# EasyEDA_Source.net
KiCad netlist of a schematic drawn in EasyEDA
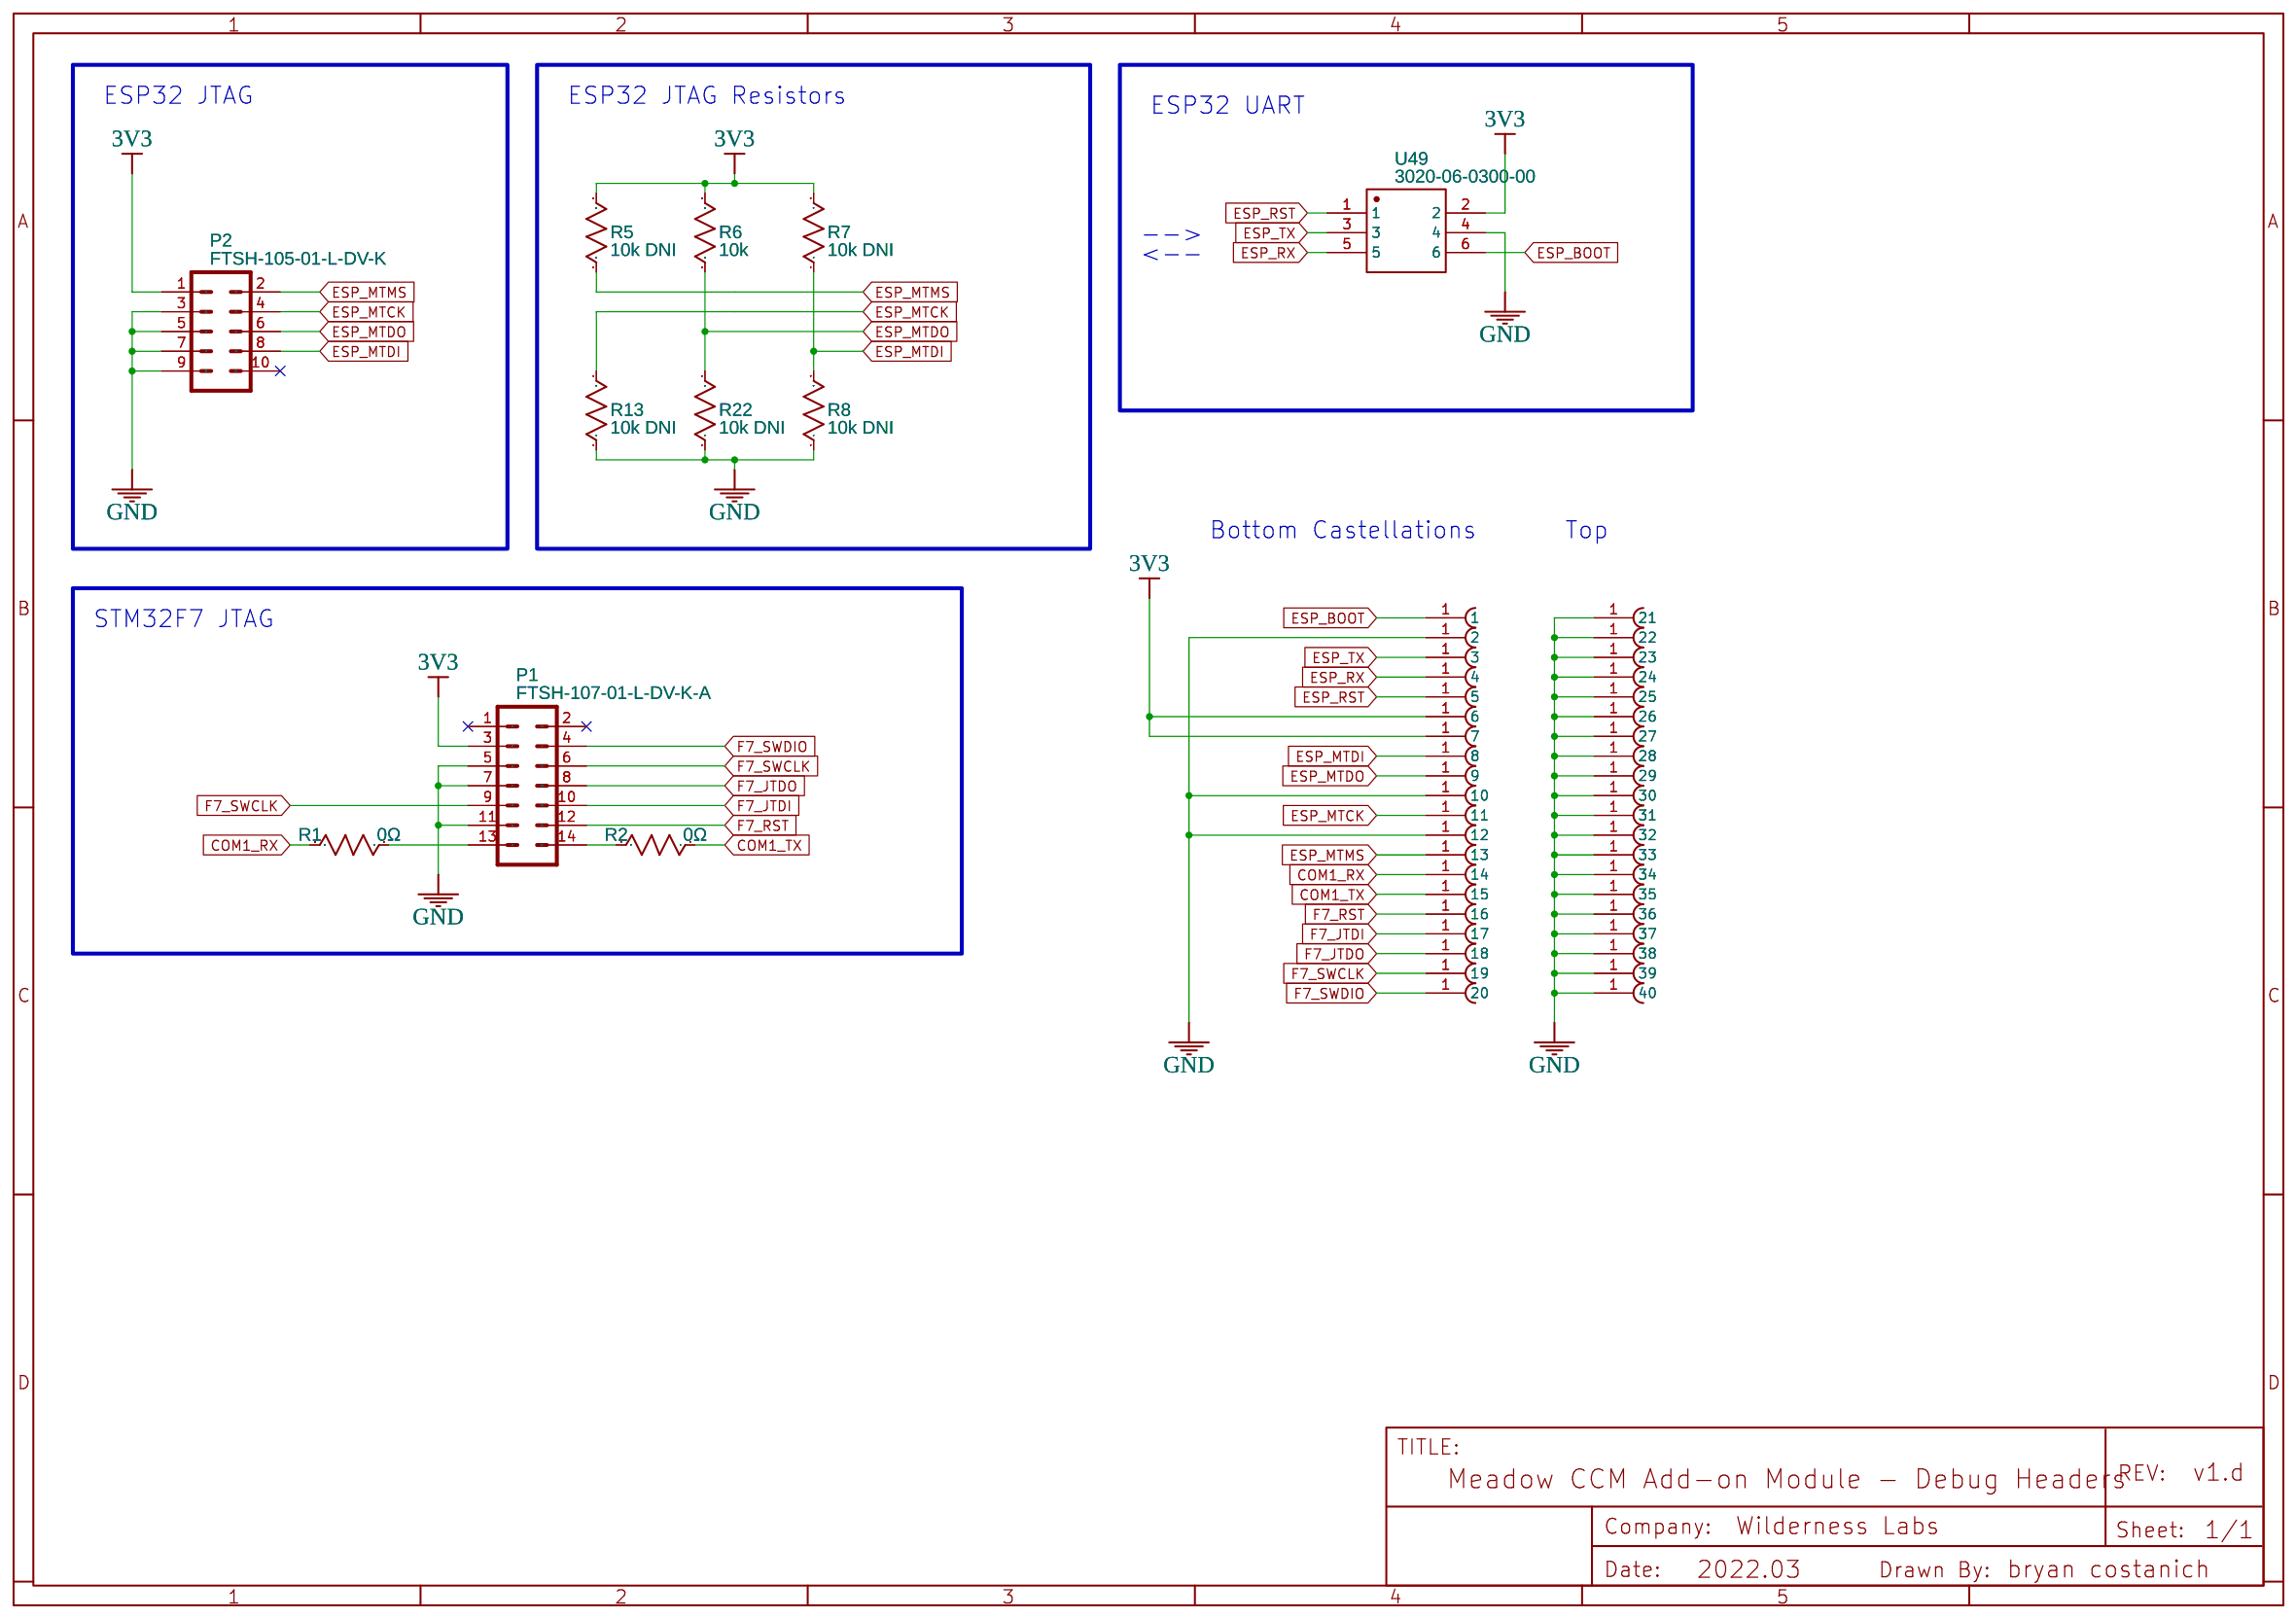
[diagram p0: schematic sheet]

(export (version "E")
  (design (tool "Eeschema 10.0.6"))
  (components
    (comp (ref "P1") (value "FTSH-107-01-L-DV-K-A") (libsource (lib "") (part "FTSH-107-01-L-DV-K-A")))
    (comp (ref "P2") (value "FTSH-105-01-L-DV-K") (libsource (lib "") (part "FTSH-105-01-L-DV-K")))
    (comp (ref "R1")
      (value "0Ω")
      (fields (field (name "BOM_Manufacturer Part") "RC0603JR-070RL"))
      (libsource (lib "") (part "R_0603_US_1"))
    )
    (comp (ref "R2")
      (value "0Ω")
      (fields (field (name "BOM_Manufacturer Part") "RC0603JR-070RL"))
      (libsource (lib "") (part "R_0603_US_1"))
    )
    (comp (ref "R5")
      (value "10k DNI")
      (fields (field (name "BOM_Manufacturer Part") "RC0603FR-0710KL"))
      (libsource (lib "") (part "R_0603_US"))
    )
    (comp (ref "R6")
      (value "10k")
      (fields (field (name "BOM_Manufacturer Part") "RC0603FR-0710KL"))
      (libsource (lib "") (part "R_0603_US"))
    )
    (comp (ref "R7")
      (value "10k DNI")
      (fields (field (name "BOM_Manufacturer Part") "RC0603FR-0710KL"))
      (libsource (lib "") (part "R_0603_US"))
    )
    (comp (ref "R8")
      (value "10k DNI")
      (fields (field (name "BOM_Manufacturer Part") "RC0603FR-0710KL"))
      (libsource (lib "") (part "R_0603_US"))
    )
    (comp (ref "R13")
      (value "10k DNI")
      (fields (field (name "BOM_Manufacturer Part") "RC0603FR-0710KL"))
      (libsource (lib "") (part "R_0603_US"))
    )
    (comp (ref "R22")
      (value "10k DNI")
      (fields (field (name "BOM_Manufacturer Part") "RC0603FR-0710KL"))
      (libsource (lib "") (part "R_0603_US"))
    )
    (comp (ref "U1") (value "1.2MM SMT Castellation") (libsource (lib "") (part "1.2MM SMT Castellation_32")))
    (comp (ref "U2") (value "1.2MM SMT Castellation") (libsource (lib "") (part "1.2MM SMT Castellation_23")))
    (comp (ref "U3") (value "1.2MM SMT Castellation") (libsource (lib "") (part "1.2MM SMT Castellation_8")))
    (comp (ref "U4") (value "1.2MM SMT Castellation") (libsource (lib "") (part "1.2MM SMT Castellation_4")))
    (comp (ref "U5") (value "1.2MM SMT Castellation") (libsource (lib "") (part "1.2MM SMT Castellation_28")))
    (comp (ref "U6") (value "1.2MM SMT Castellation") (libsource (lib "") (part "1.2MM SMT Castellation_26")))
    (comp (ref "U7") (value "1.2MM SMT Castellation") (libsource (lib "") (part "1.2MM SMT Castellation_31")))
    (comp (ref "U8") (value "1.2MM SMT Castellation") (libsource (lib "") (part "1.2MM SMT Castellation_10")))
    (comp (ref "U9") (value "1.2MM SMT Castellation") (libsource (lib "") (part "1.2MM SMT Castellation_35")))
    (comp (ref "U10") (value "1.2MM SMT Castellation") (libsource (lib "") (part "1.2MM SMT Castellation_9")))
    (comp (ref "U11")
      (value "1.2MM SMT Castellation")
      (libsource (lib "") (part "1.2MM SMT Castellation_16"))
    )
    (comp (ref "U12")
      (value "1.2MM SMT Castellation")
      (libsource (lib "") (part "1.2MM SMT Castellation_37"))
    )
    (comp (ref "U13") (value "1.2MM SMT Castellation") (libsource (lib "") (part "1.2MM SMT Castellation_7")))
    (comp (ref "U14")
      (value "1.2MM SMT Castellation")
      (libsource (lib "") (part "1.2MM SMT Castellation_14"))
    )
    (comp (ref "U15") (value "1.2MM SMT Castellation") (libsource (lib "") (part "1.2MM SMT Castellation_3")))
    (comp (ref "U16")
      (value "1.2MM SMT Castellation")
      (libsource (lib "") (part "1.2MM SMT Castellation_22"))
    )
    (comp (ref "U17")
      (value "1.2MM SMT Castellation")
      (libsource (lib "") (part "1.2MM SMT Castellation_18"))
    )
    (comp (ref "U18")
      (value "1.2MM SMT Castellation")
      (libsource (lib "") (part "1.2MM SMT Castellation_13"))
    )
    (comp (ref "U19")
      (value "1.2MM SMT Castellation")
      (libsource (lib "") (part "1.2MM SMT Castellation_34"))
    )
    (comp (ref "U20")
      (value "1.2MM SMT Castellation")
      (libsource (lib "") (part "1.2MM SMT Castellation_11"))
    )
    (comp (ref "U21")
      (value "1.2MM SMT Castellation")
      (libsource (lib "") (part "1.2MM SMT Castellation_39"))
    )
    (comp (ref "U22") (value "1.2MM SMT Castellation") (libsource (lib "") (part "1.2MM SMT Castellation_5")))
    (comp (ref "U23")
      (value "1.2MM SMT Castellation")
      (libsource (lib "") (part "1.2MM SMT Castellation_25"))
    )
    (comp (ref "U24")
      (value "1.2MM SMT Castellation")
      (libsource (lib "") (part "1.2MM SMT Castellation_36"))
    )
    (comp (ref "U25")
      (value "1.2MM SMT Castellation")
      (libsource (lib "") (part "1.2MM SMT Castellation_19"))
    )
    (comp (ref "U26")
      (value "1.2MM SMT Castellation")
      (libsource (lib "") (part "1.2MM SMT Castellation_33"))
    )
    (comp (ref "U27")
      (value "1.2MM SMT Castellation")
      (libsource (lib "") (part "1.2MM SMT Castellation_30"))
    )
    (comp (ref "U28")
      (value "1.2MM SMT Castellation")
      (libsource (lib "") (part "1.2MM SMT Castellation_29"))
    )
    (comp (ref "U29")
      (value "1.2MM SMT Castellation")
      (libsource (lib "") (part "1.2MM SMT Castellation_17"))
    )
    (comp (ref "U30") (value "1.2MM SMT Castellation") (libsource (lib "") (part "1.2MM SMT Castellation_1")))
    (comp (ref "U31") (value "1.2MM SMT Castellation") (libsource (lib "") (part "1.2MM SMT Castellation_6")))
    (comp (ref "U32") (value "1.2MM SMT Castellation") (libsource (lib "") (part "1.2MM SMT Castellation")))
    (comp (ref "U33")
      (value "1.2MM SMT Castellation")
      (libsource (lib "") (part "1.2MM SMT Castellation_21"))
    )
    (comp (ref "U34") (value "1.2MM SMT Castellation") (libsource (lib "") (part "1.2MM SMT Castellation_2")))
    (comp (ref "U35")
      (value "1.2MM SMT Castellation")
      (libsource (lib "") (part "1.2MM SMT Castellation_38"))
    )
    (comp (ref "U36")
      (value "1.2MM SMT Castellation")
      (libsource (lib "") (part "1.2MM SMT Castellation_24"))
    )
    (comp (ref "U37")
      (value "1.2MM SMT Castellation")
      (libsource (lib "") (part "1.2MM SMT Castellation_20"))
    )
    (comp (ref "U38")
      (value "1.2MM SMT Castellation")
      (libsource (lib "") (part "1.2MM SMT Castellation_12"))
    )
    (comp (ref "U39")
      (value "1.2MM SMT Castellation")
      (libsource (lib "") (part "1.2MM SMT Castellation_27"))
    )
    (comp (ref "U49")
      (value "3020-06-0300-00")
      (fields (field (name "BOM_Supplier Part") "1175-1864-ND"))
      (libsource (lib "") (part "3020-06-0300-00"))
    )
    (comp (ref "U53")
      (value "1.2MM SMT Castellation")
      (libsource (lib "") (part "1.2MM SMT Castellation_15"))
    )
  )
  (nets
    (net (code "1") (name "3V3") (class "Default")
      (node (ref "P1") (pin "3") (pinfunction "3_3") (pintype "unspecified"))
      (node (ref "P2") (pin "1") (pinfunction "1_1") (pintype "unspecified"))
      (node (ref "R5") (pin "2") (pinfunction "2_2") (pintype "unspecified"))
      (node (ref "R6") (pin "2") (pinfunction "2_2") (pintype "unspecified"))
      (node (ref "R7") (pin "2") (pinfunction "2_2") (pintype "unspecified"))
      (node (ref "U49") (pin "2") (pinfunction "2_2") (pintype "unspecified"))
      (node (ref "U6") (pin "1") (pinfunction "6_1") (pintype "unspecified"))
      (node (ref "U7") (pin "1") (pinfunction "7_1") (pintype "unspecified"))
    )
    (net (code "2") (name "COM1_RX") (class "Default")
      (node (ref "R1") (pin "2") (pinfunction "2_2") (pintype "unspecified"))
      (node (ref "U14") (pin "1") (pinfunction "14_1") (pintype "unspecified"))
    )
    (net (code "3") (name "COM1_TX") (class "Default")
      (node (ref "R2") (pin "1") (pinfunction "1_1") (pintype "unspecified"))
      (node (ref "U15") (pin "1") (pinfunction "15_1") (pintype "unspecified"))
    )
    (net (code "4") (name "ESP_BOOT") (class "Default")
      (node (ref "U49") (pin "6") (pinfunction "6_6") (pintype "unspecified"))
      (node (ref "U53") (pin "1") (pinfunction "1_1") (pintype "unspecified"))
    )
    (net (code "5") (name "ESP_MTCK") (class "Default")
      (node (ref "P2") (pin "4") (pinfunction "4_4") (pintype "unspecified"))
      (node (ref "R13") (pin "2") (pinfunction "2_2") (pintype "unspecified"))
      (node (ref "U11") (pin "1") (pinfunction "11_1") (pintype "unspecified"))
    )
    (net (code "6") (name "ESP_MTDI") (class "Default")
      (node (ref "P2") (pin "8") (pinfunction "8_8") (pintype "unspecified"))
      (node (ref "R7") (pin "1") (pinfunction "1_1") (pintype "unspecified"))
      (node (ref "R8") (pin "2") (pinfunction "2_2") (pintype "unspecified"))
      (node (ref "U8") (pin "1") (pinfunction "8_1") (pintype "unspecified"))
    )
    (net (code "7") (name "ESP_MTDO") (class "Default")
      (node (ref "P2") (pin "6") (pinfunction "6_6") (pintype "unspecified"))
      (node (ref "R22") (pin "2") (pinfunction "2_2") (pintype "unspecified"))
      (node (ref "R6") (pin "1") (pinfunction "1_1") (pintype "unspecified"))
      (node (ref "U9") (pin "1") (pinfunction "9_1") (pintype "unspecified"))
    )
    (net (code "8") (name "ESP_MTMS") (class "Default")
      (node (ref "P2") (pin "2") (pinfunction "2_2") (pintype "unspecified"))
      (node (ref "R5") (pin "1") (pinfunction "1_1") (pintype "unspecified"))
      (node (ref "U13") (pin "1") (pinfunction "13_1") (pintype "unspecified"))
    )
    (net (code "9") (name "ESP_RST") (class "Default")
      (node (ref "U4") (pin "1") (pinfunction "5_1") (pintype "unspecified"))
      (node (ref "U49") (pin "1") (pinfunction "1_1") (pintype "unspecified"))
    )
    (net (code "10") (name "ESP_RX") (class "Default")
      (node (ref "U3") (pin "1") (pinfunction "4_1") (pintype "unspecified"))
      (node (ref "U49") (pin "5") (pinfunction "5_5") (pintype "unspecified"))
    )
    (net (code "11") (name "ESP_TX") (class "Default")
      (node (ref "U2") (pin "1") (pinfunction "3_1") (pintype "unspecified"))
      (node (ref "U49") (pin "3") (pinfunction "3_3") (pintype "unspecified"))
    )
    (net (code "12") (name "F7_JTDI") (class "Default")
      (node (ref "P1") (pin "10") (pinfunction "10_10") (pintype "unspecified"))
      (node (ref "U18") (pin "1") (pinfunction "17_1") (pintype "unspecified"))
    )
    (net (code "13") (name "F7_JTDO") (class "Default")
      (node (ref "P1") (pin "8") (pinfunction "8_8") (pintype "unspecified"))
      (node (ref "U30") (pin "1") (pinfunction "18_1") (pintype "unspecified"))
    )
    (net (code "14") (name "F7_RST") (class "Default")
      (node (ref "P1") (pin "12") (pinfunction "12_12") (pintype "unspecified"))
      (node (ref "U16") (pin "1") (pinfunction "16_1") (pintype "unspecified"))
    )
    (net (code "15") (name "F7_SWCLK") (class "Default")
      (node (ref "P1") (pin "6") (pinfunction "6_6") (pintype "unspecified"))
      (node (ref "P1") (pin "9") (pinfunction "9_9") (pintype "unspecified"))
      (node (ref "U35") (pin "1") (pinfunction "19_1") (pintype "unspecified"))
    )
    (net (code "16") (name "F7_SWDIO") (class "Default")
      (node (ref "P1") (pin "4") (pinfunction "4_4") (pintype "unspecified"))
      (node (ref "U36") (pin "1") (pinfunction "20_1") (pintype "unspecified"))
    )
    (net (code "17") (name "GND") (class "Default")
      (node (ref "P1") (pin "11") (pinfunction "11_11") (pintype "unspecified"))
      (node (ref "P1") (pin "5") (pinfunction "5_5") (pintype "unspecified"))
      (node (ref "P1") (pin "7") (pinfunction "7_7") (pintype "unspecified"))
      (node (ref "P2") (pin "3") (pinfunction "3_3") (pintype "unspecified"))
      (node (ref "P2") (pin "5") (pinfunction "5_5") (pintype "unspecified"))
      (node (ref "P2") (pin "7") (pinfunction "7_7") (pintype "unspecified"))
      (node (ref "P2") (pin "9") (pinfunction "9_9") (pintype "unspecified"))
      (node (ref "R13") (pin "1") (pinfunction "1_1") (pintype "unspecified"))
      (node (ref "R22") (pin "1") (pinfunction "1_1") (pintype "unspecified"))
      (node (ref "R8") (pin "1") (pinfunction "1_1") (pintype "unspecified"))
      (node (ref "U1") (pin "1") (pinfunction "2_1") (pintype "unspecified"))
      (node (ref "U10") (pin "1") (pinfunction "10_1") (pintype "unspecified"))
      (node (ref "U12") (pin "1") (pinfunction "12_1") (pintype "unspecified"))
      (node (ref "U17") (pin "1") (pinfunction "22_1") (pintype "unspecified"))
      (node (ref "U19") (pin "1") (pinfunction "23_1") (pintype "unspecified"))
      (node (ref "U20") (pin "1") (pinfunction "24_1") (pintype "unspecified"))
      (node (ref "U21") (pin "1") (pinfunction "25_1") (pintype "unspecified"))
      (node (ref "U22") (pin "1") (pinfunction "26_1") (pintype "unspecified"))
      (node (ref "U23") (pin "1") (pinfunction "27_1") (pintype "unspecified"))
      (node (ref "U24") (pin "1") (pinfunction "28_1") (pintype "unspecified"))
      (node (ref "U25") (pin "1") (pinfunction "29_1") (pintype "unspecified"))
      (node (ref "U26") (pin "1") (pinfunction "30_1") (pintype "unspecified"))
      (node (ref "U27") (pin "1") (pinfunction "31_1") (pintype "unspecified"))
      (node (ref "U28") (pin "1") (pinfunction "32_1") (pintype "unspecified"))
      (node (ref "U29") (pin "1") (pinfunction "33_1") (pintype "unspecified"))
      (node (ref "U31") (pin "1") (pinfunction "34_1") (pintype "unspecified"))
      (node (ref "U32") (pin "1") (pinfunction "35_1") (pintype "unspecified"))
      (node (ref "U33") (pin "1") (pinfunction "36_1") (pintype "unspecified"))
      (node (ref "U34") (pin "1") (pinfunction "37_1") (pintype "unspecified"))
      (node (ref "U37") (pin "1") (pinfunction "38_1") (pintype "unspecified"))
      (node (ref "U38") (pin "1") (pinfunction "39_1") (pintype "unspecified"))
      (node (ref "U39") (pin "1") (pinfunction "40_1") (pintype "unspecified"))
      (node (ref "U49") (pin "4") (pinfunction "4_4") (pintype "unspecified"))
      (node (ref "U5") (pin "1") (pinfunction "21_1") (pintype "unspecified"))
    )
    (net (code "18") (name "Net-(P1-Pad13)") (class "Default")
      (node (ref "P1") (pin "13") (pinfunction "13_13") (pintype "unspecified"))
      (node (ref "R1") (pin "1") (pinfunction "1_1") (pintype "unspecified"))
    )
    (net (code "19") (name "Net-(P1-Pad14)") (class "Default")
      (node (ref "P1") (pin "14") (pinfunction "14_14") (pintype "unspecified"))
      (node (ref "R2") (pin "2") (pinfunction "2_2") (pintype "unspecified"))
    )
    (net (code "20") (name "unconnected-(P1-Pad1)") (class "Default")
      (node (ref "P1") (pin "1") (pinfunction "1_1") (pintype "unspecified+no_connect"))
    )
    (net (code "21") (name "unconnected-(P1-Pad2)") (class "Default")
      (node (ref "P1") (pin "2") (pinfunction "2_2") (pintype "unspecified+no_connect"))
    )
    (net (code "22") (name "unconnected-(P2-Pad10)") (class "Default")
      (node (ref "P2") (pin "10") (pinfunction "10_10") (pintype "unspecified+no_connect"))
    )
  )
)
